# node-test-array__TOP_LEVEL__B.net
KiCad netlist of a schematic drawn in Altium Designer
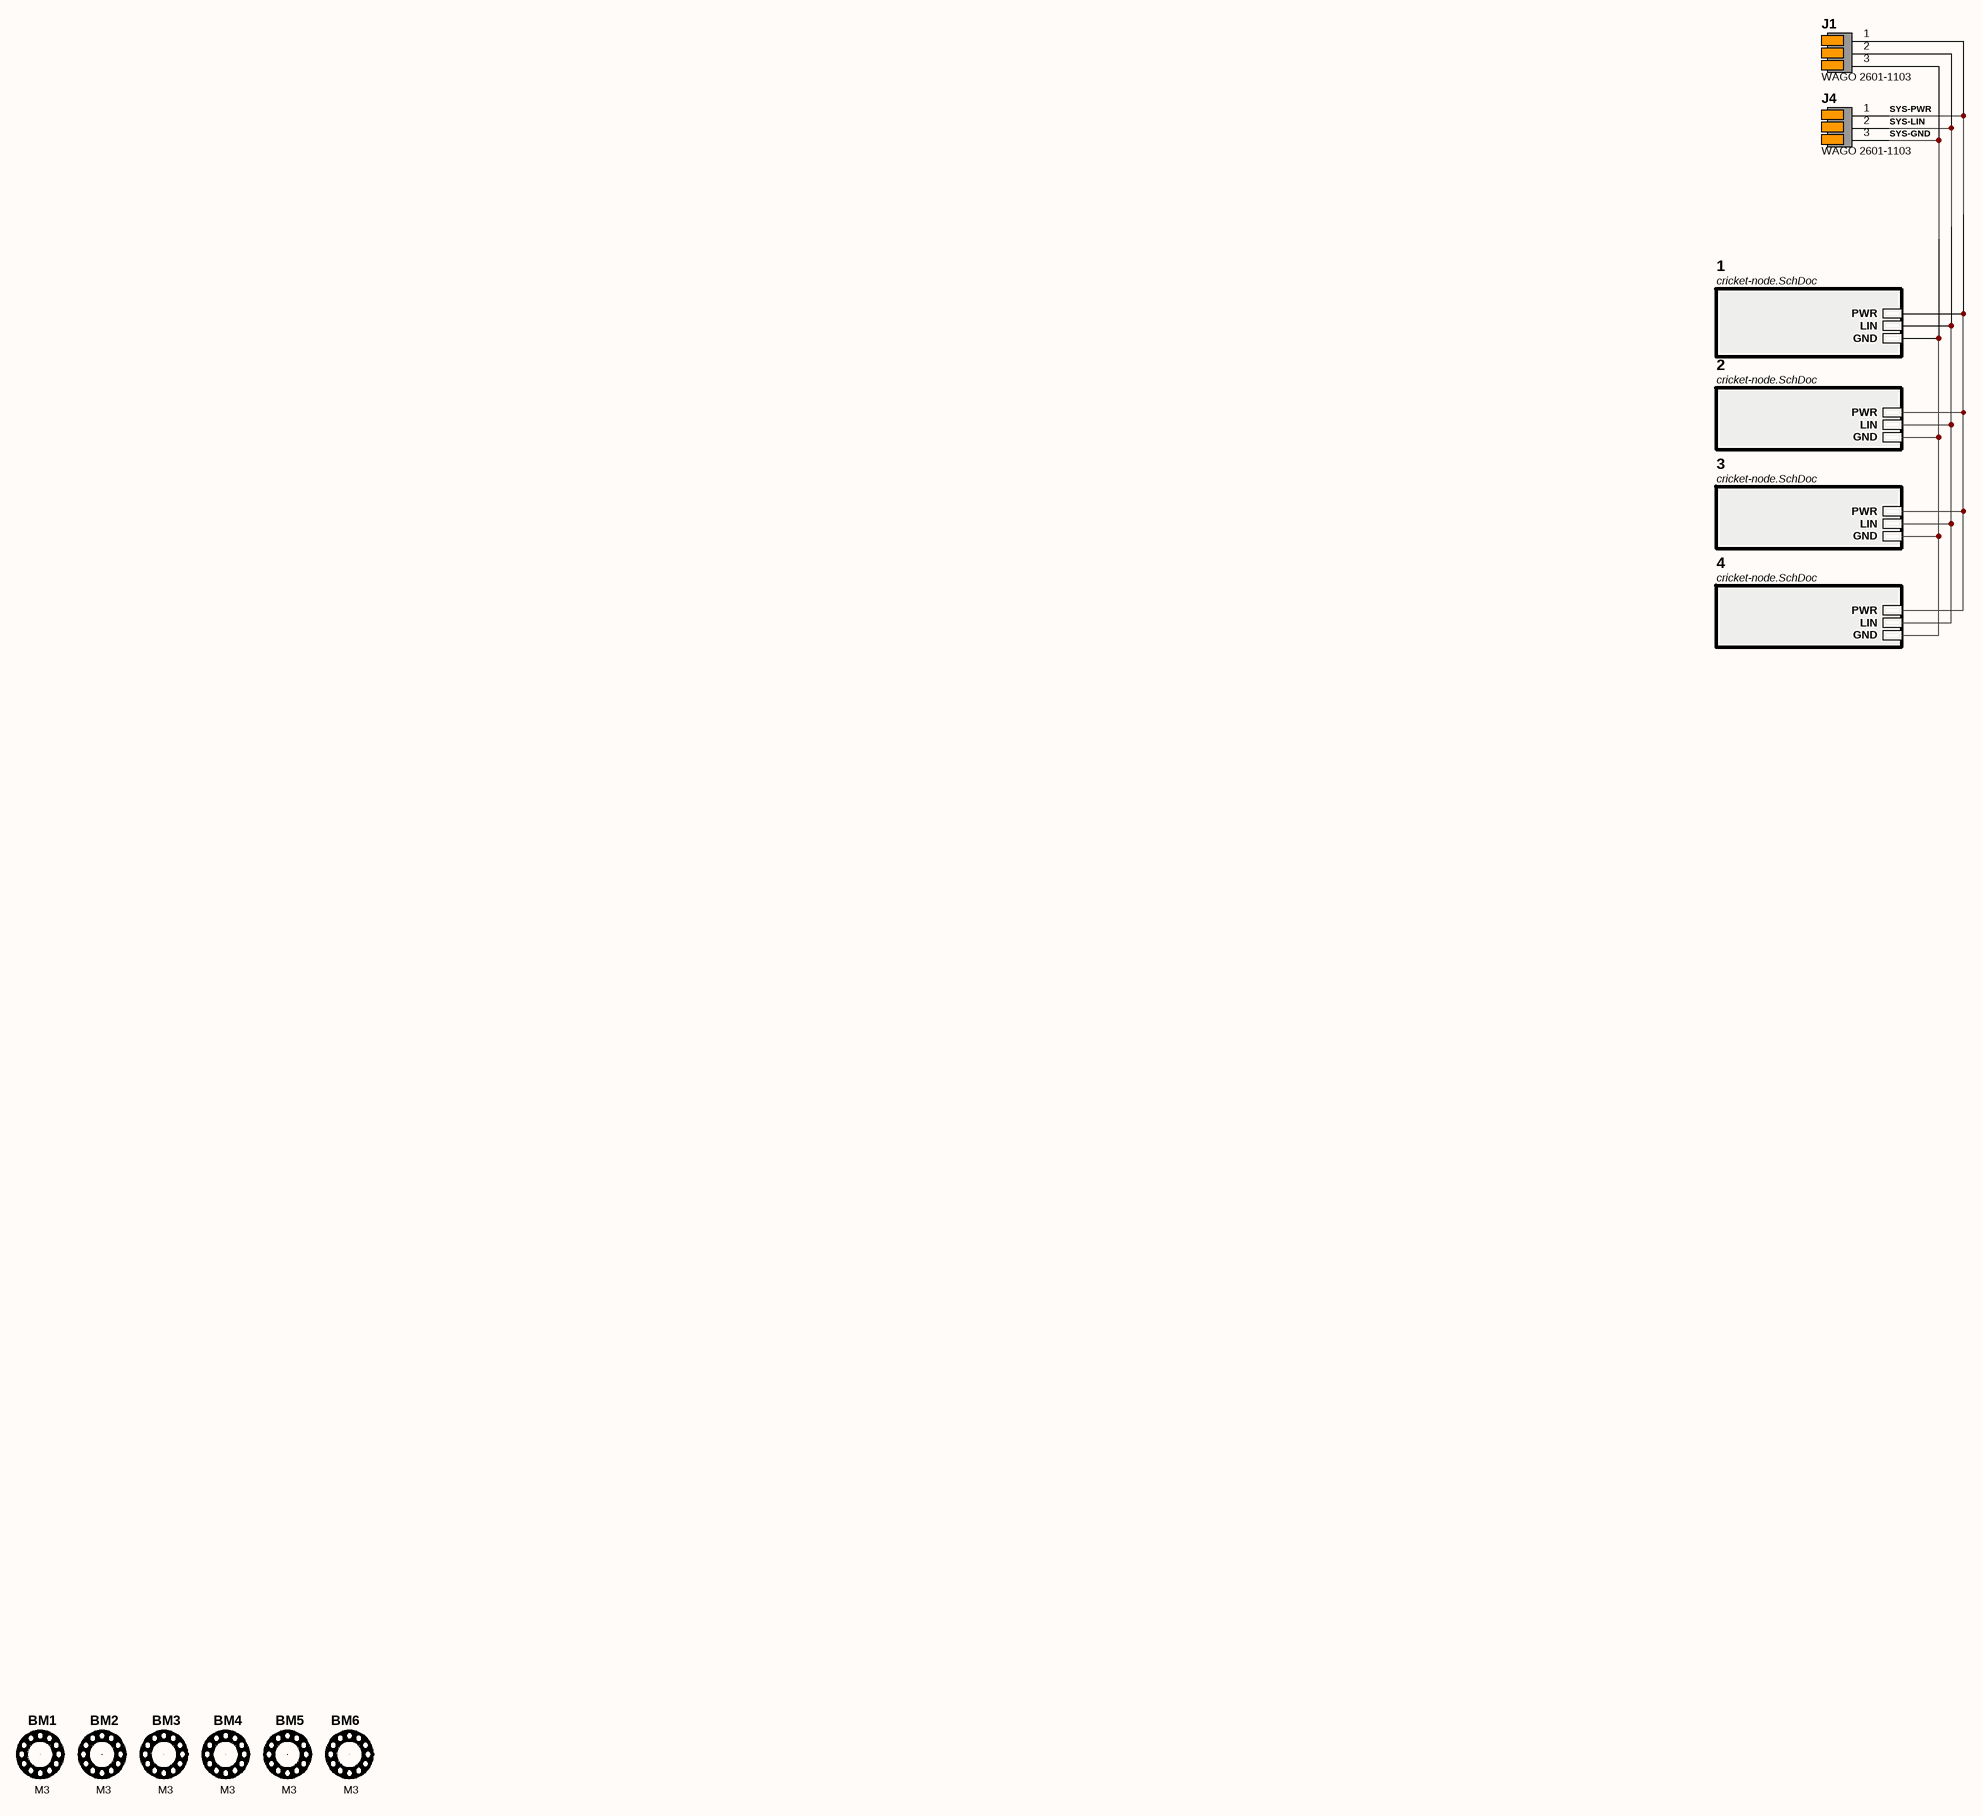
[diagram p0: node-test-array__TOP_LEVEL__B.SchDoc]

(export (version "E")
  (design (tool "Eeschema 10.0.6"))
  (components
    (comp (ref "BM1")
      (value "M3")
      (footprint "M3")
      (description "M3 screw hole ISO standard 3.6mm clearance 16 conductivity holes 6.3mm pad size")
      (fields (field (name "MANUFACTURER") "Wavenumber"))
      (libsource (lib "mechanical") (part "screw-hole"))
    )
    (comp (ref "BM2")
      (value "M3")
      (footprint "M3")
      (description "M3 screw hole ISO standard 3.6mm clearance 16 conductivity holes 6.3mm pad size")
      (fields (field (name "MANUFACTURER") "Wavenumber"))
      (libsource (lib "mechanical") (part "screw-hole"))
    )
    (comp (ref "BM3")
      (value "M3")
      (footprint "M3")
      (description "M3 screw hole ISO standard 3.6mm clearance 16 conductivity holes 6.3mm pad size")
      (fields (field (name "MANUFACTURER") "Wavenumber"))
      (libsource (lib "mechanical") (part "screw-hole"))
    )
    (comp (ref "BM4")
      (value "M3")
      (footprint "M3")
      (description "M3 screw hole ISO standard 3.6mm clearance 16 conductivity holes 6.3mm pad size")
      (fields (field (name "MANUFACTURER") "Wavenumber"))
      (libsource (lib "mechanical") (part "screw-hole"))
    )
    (comp (ref "BM5")
      (value "M3")
      (footprint "M3")
      (description "M3 screw hole ISO standard 3.6mm clearance 16 conductivity holes 6.3mm pad size")
      (fields (field (name "MANUFACTURER") "Wavenumber"))
      (libsource (lib "mechanical") (part "screw-hole"))
    )
    (comp (ref "BM6")
      (value "M3")
      (footprint "M3")
      (description "M3 screw hole ISO standard 3.6mm clearance 16 conductivity holes 6.3mm pad size")
      (fields (field (name "MANUFACTURER") "Wavenumber"))
      (libsource (lib "mechanical") (part "screw-hole"))
    )
    (comp (ref "J1")
      (value "WAGO 2601-1103")
      (footprint "2601-1103")
      (description "3 Position Wire to Board Terminal Block Horizontal with Board 0.137\" (3.50mm) Through Hole")
      (fields (field (name "INTERNAL PART NUMBER") "2601-1103") (field (name "MANUFACTURER") "Wago"))
      (libsource (lib "connector") (part "2601-1103"))
    )
    (comp (ref "J4")
      (value "WAGO 2601-1103")
      (footprint "2601-1103")
      (description "3 Position Wire to Board Terminal Block Horizontal with Board 0.137\" (3.50mm) Through Hole")
      (fields (field (name "INTERNAL PART NUMBER") "2601-1103") (field (name "MANUFACTURER") "Wago"))
      (libsource (lib "connector") (part "2601-1103"))
    )
  )
  (nets
    (net (code "1") (name "/SYS-GND") (class "Default")
      (node (ref "J1") (pin "3") (pinfunction "3_3") (pintype "passive"))
      (node (ref "J4") (pin "3") (pinfunction "3_3") (pintype "passive"))
    )
    (net (code "2") (name "/SYS-LIN") (class "Default")
      (node (ref "J1") (pin "2") (pinfunction "2_2") (pintype "passive"))
      (node (ref "J4") (pin "2") (pinfunction "2_2") (pintype "passive"))
    )
    (net (code "3") (name "/SYS-PWR") (class "Default")
      (node (ref "J1") (pin "1") (pinfunction "1_1") (pintype "passive"))
      (node (ref "J4") (pin "1") (pinfunction "1_1") (pintype "passive"))
    )
    (net (code "4") (name "unconnected-(BM1-Pad1)") (class "Default")
      (node (ref "BM1") (pin "1") (pinfunction "1_1") (pintype "passive"))
    )
    (net (code "5") (name "unconnected-(BM2-Pad1)") (class "Default")
      (node (ref "BM2") (pin "1") (pinfunction "1_1") (pintype "passive"))
    )
    (net (code "6") (name "unconnected-(BM3-Pad1)") (class "Default")
      (node (ref "BM3") (pin "1") (pinfunction "1_1") (pintype "passive"))
    )
    (net (code "7") (name "unconnected-(BM4-Pad1)") (class "Default")
      (node (ref "BM4") (pin "1") (pinfunction "1_1") (pintype "passive"))
    )
    (net (code "8") (name "unconnected-(BM5-Pad1)") (class "Default")
      (node (ref "BM5") (pin "1") (pinfunction "1_1") (pintype "passive"))
    )
    (net (code "9") (name "unconnected-(BM6-Pad1)") (class "Default")
      (node (ref "BM6") (pin "1") (pinfunction "1_1") (pintype "passive"))
    )
  )
)
